# MainSch.net
KiCad netlist of a schematic drawn in Altium Designer
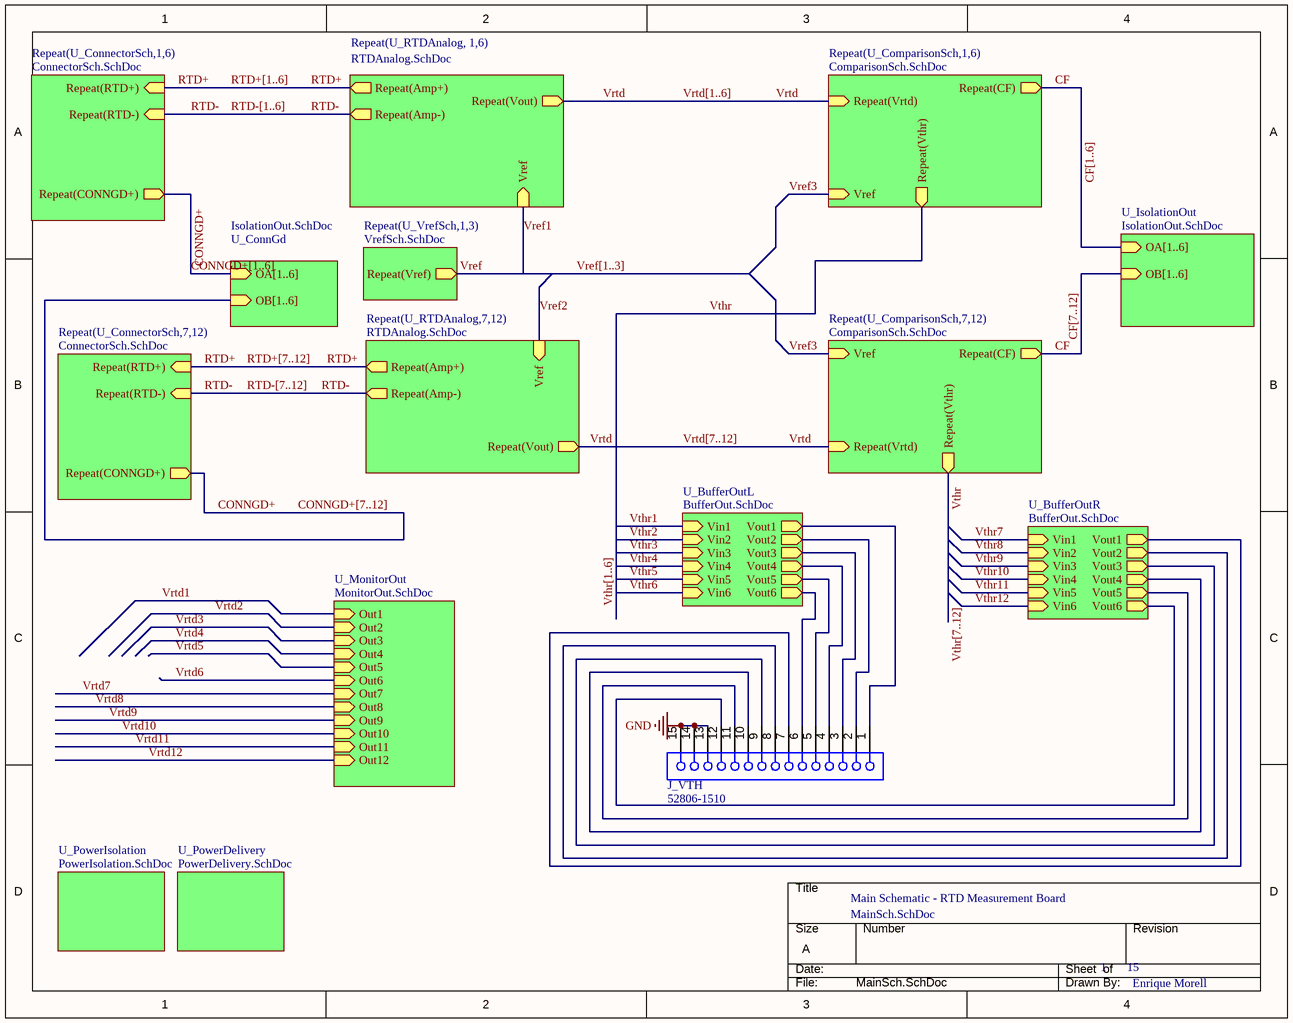
[diagram p0: MainSch.SchDoc]

(export (version "E")
  (design (tool "Eeschema 10.0.6"))
  (components
    (comp (ref "J_VTH")
      (value "52806-1510")
      (footprint "MOLX-52806-1510")
      (fields (field (name "MANUFACTURER") "Molex"))
      (libsource (lib "Altium Content Vault") (part "MOLX-52806-1510"))
    )
  )
  (nets
    (net (code "61") (name "/Vout1") (class "Default")
      (node (ref "J_VTH") (pin "7") (pinfunction "7_7") (pintype "passive"))
    )
    (net (code "62") (name "/Vout1_1") (class "Default")
      (node (ref "J_VTH") (pin "1") (pinfunction "1_1") (pintype "passive"))
    )
    (net (code "63") (name "/Vout2") (class "Default")
      (node (ref "J_VTH") (pin "8") (pinfunction "8_8") (pintype "passive"))
    )
    (net (code "64") (name "/Vout2_1") (class "Default")
      (node (ref "J_VTH") (pin "2") (pinfunction "2_2") (pintype "passive"))
    )
    (net (code "65") (name "/Vout3") (class "Default")
      (node (ref "J_VTH") (pin "9") (pinfunction "9_9") (pintype "passive"))
    )
    (net (code "66") (name "/Vout3_1") (class "Default")
      (node (ref "J_VTH") (pin "3") (pinfunction "3_3") (pintype "passive"))
    )
    (net (code "67") (name "/Vout4") (class "Default")
      (node (ref "J_VTH") (pin "4") (pinfunction "4_4") (pintype "passive"))
    )
    (net (code "68") (name "/Vout4_1") (class "Default")
      (node (ref "J_VTH") (pin "10") (pinfunction "10_10") (pintype "passive"))
    )
    (net (code "69") (name "/Vout5") (class "Default")
      (node (ref "J_VTH") (pin "5") (pinfunction "5_5") (pintype "passive"))
    )
    (net (code "70") (name "/Vout5_1") (class "Default")
      (node (ref "J_VTH") (pin "11") (pinfunction "11_11") (pintype "passive"))
    )
    (net (code "71") (name "/Vout6") (class "Default")
      (node (ref "J_VTH") (pin "6") (pinfunction "6_6") (pintype "passive"))
    )
    (net (code "72") (name "/Vout6_1") (class "Default")
      (node (ref "J_VTH") (pin "12") (pinfunction "12_12") (pintype "passive"))
    )
    (net (code "108") (name "GND") (class "Default")
      (node (ref "J_VTH") (pin "13") (pinfunction "13_13") (pintype "passive"))
      (node (ref "J_VTH") (pin "14") (pinfunction "14_14") (pintype "passive"))
      (node (ref "J_VTH") (pin "15") (pinfunction "15_15") (pintype "passive"))
    )
  )
)
